# AC2_Measure.net
KiCad netlist of a schematic drawn in Altium Designer
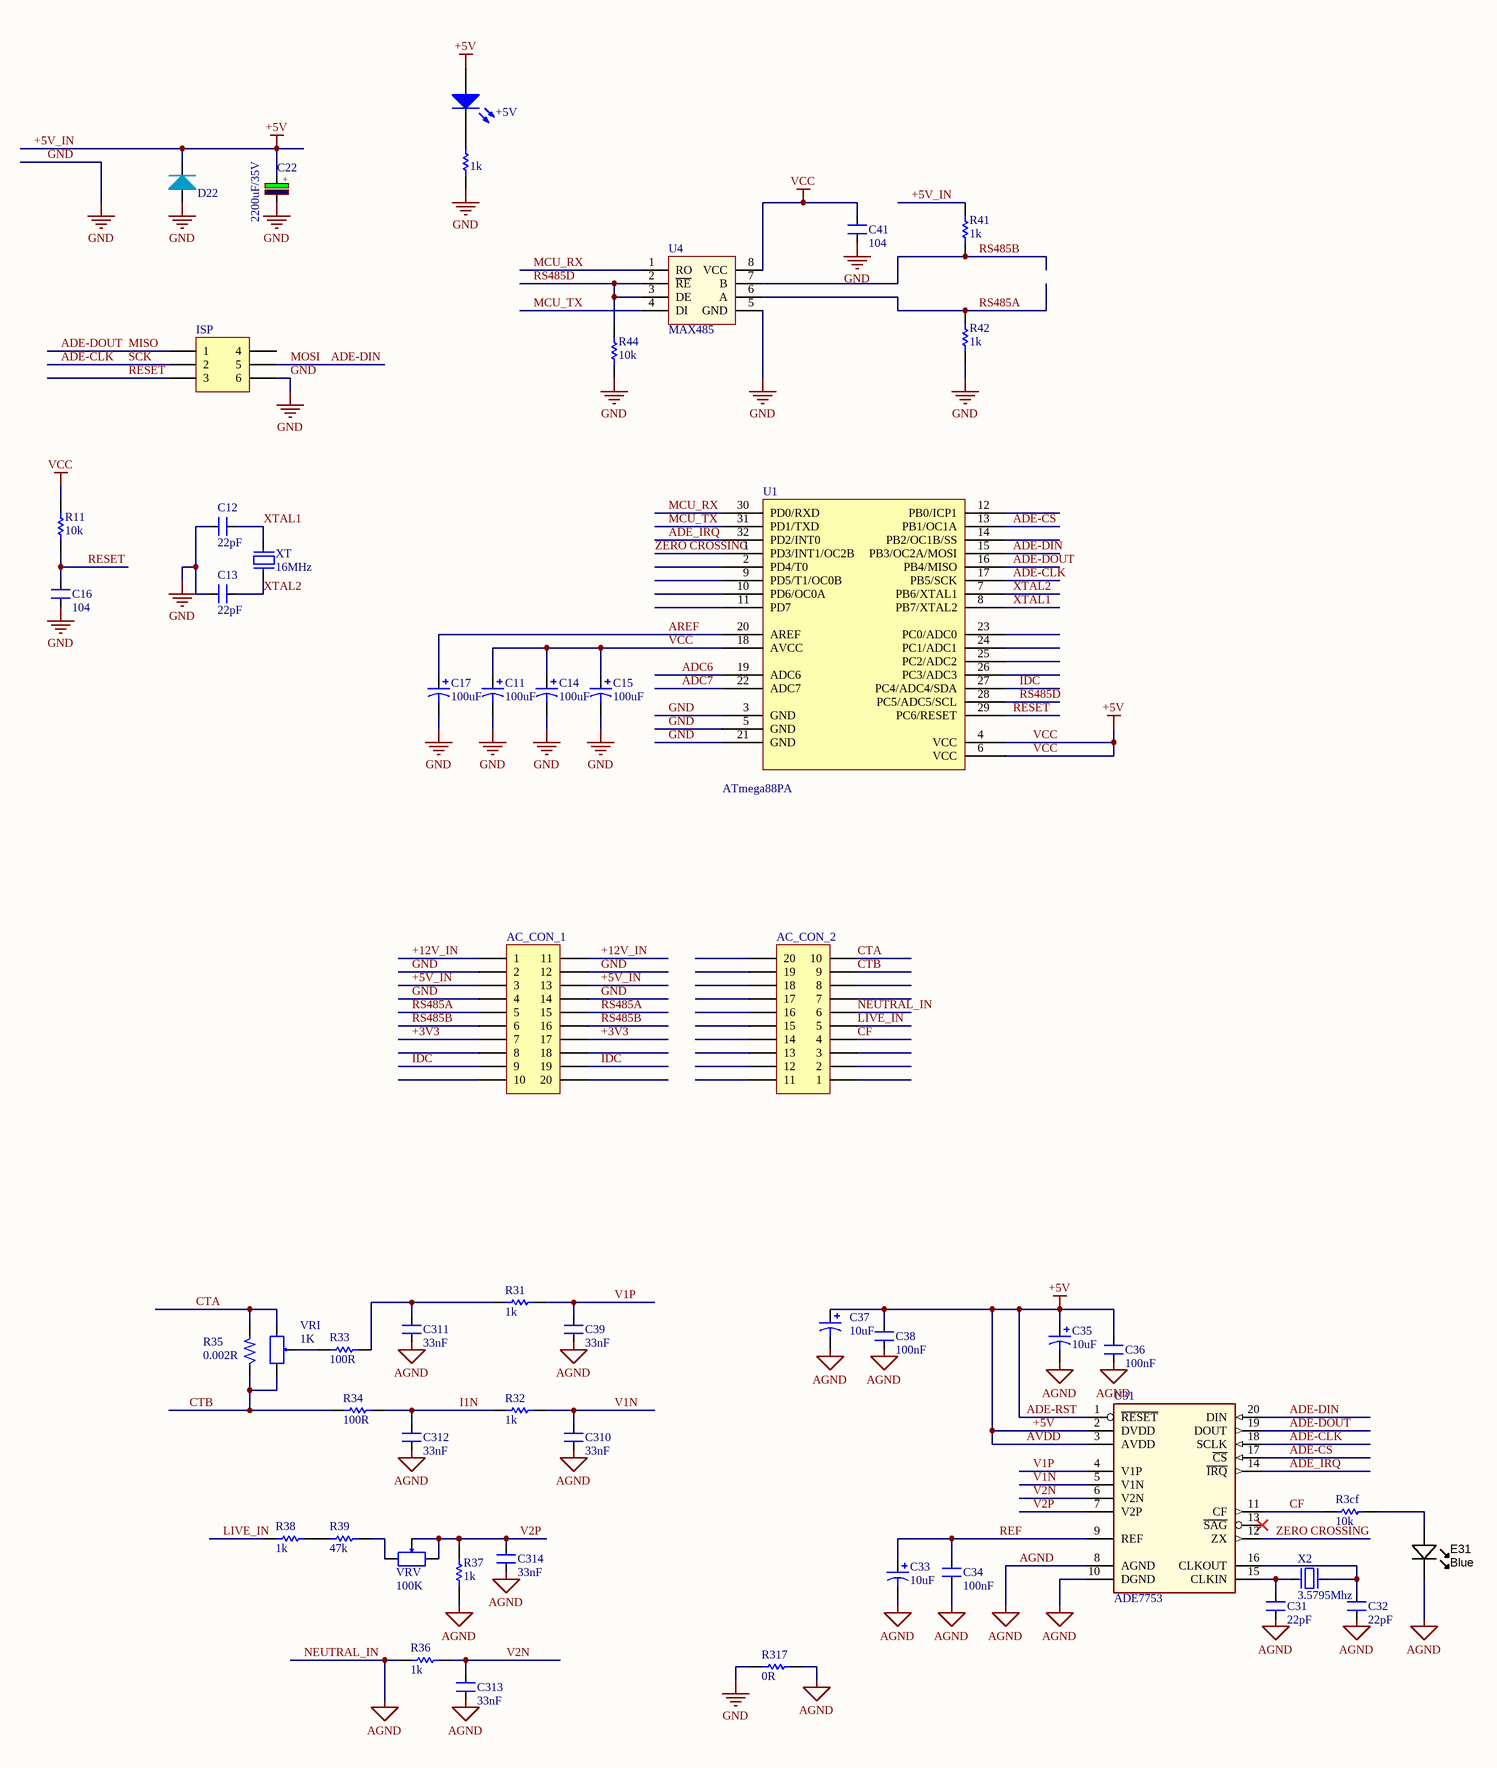
[diagram p0: AC2_Measure.SchDoc]

(export (version "E")
  (design (tool "Eeschema 10.0.6"))
  (components
    (comp (ref "+5V") (value "Led") (footprint "LED 5mm RED") (libsource (lib "Tuan") (part "Led")))
    (comp (ref "AC_CON_1")
      (value "Header 10X2A")
      (footprint "OMC10")
      (description "Header, 10-Pin, Dual row")
      (fields (field (name "PUBLISHER") "Altium Limited"))
      (libsource (lib "Miscellaneous Connectors") (part "Header 10X2A"))
    )
    (comp (ref "AC_CON_2")
      (value "Header 10X2A")
      (footprint "OMC10")
      (description "Header, 10-Pin, Dual row")
      (fields (field (name "PUBLISHER") "Altium Limited"))
      (libsource (lib "") (part "Header 10X2A_1"))
    )
    (comp (ref "C11")
      (value "100uF")
      (footprint "CAPC2012N_F")
      (fields (field (name "Comment") "Cap"))
      (libsource (lib "Tuan") (part "Cap"))
    )
    (comp (ref "C12")
      (value "22pF")
      (footprint "CAPC1608N")
      (fields (field (name "Comment") "CAP NP"))
      (libsource (lib "Tuan") (part "CAP NP"))
    )
    (comp (ref "C13")
      (value "22pF")
      (footprint "CAPC1608N")
      (fields (field (name "Comment") "CAP NP"))
      (libsource (lib "Tuan") (part "CAP NP"))
    )
    (comp (ref "C14")
      (value "100uF")
      (footprint "CAPC2012N_F")
      (fields (field (name "Comment") "Cap"))
      (libsource (lib "Tuan") (part "Cap"))
    )
    (comp (ref "C15")
      (value "100uF")
      (footprint "CAPC2012N_F")
      (fields (field (name "Comment") "Cap"))
      (libsource (lib "Tuan") (part "Cap"))
    )
    (comp (ref "C16")
      (value "104")
      (footprint "CAPC1608N")
      (fields (field (name "Comment") "CAP NP"))
      (libsource (lib "Tuan") (part "CAP NP"))
    )
    (comp (ref "C17")
      (value "100uF")
      (footprint "CAPC2012N_F")
      (fields (field (name "Comment") "Cap"))
      (libsource (lib "Tuan") (part "Cap"))
    )
    (comp (ref "C22")
      (value "2200uF/35V")
      (footprint "PBL - SMD Packages:CAP_ELEC_SIZE_G")
      (description "Cap 1000uF/16V - 220uF/50V")
      (libsource (lib "heromap") (part "CP4"))
    )
    (comp (ref "C31")
      (value "22pF")
      (footprint "CAPC1608N")
      (fields (field (name "Comment") "CAP NP"))
      (libsource (lib "ELS-PLC-2.0") (part "CAP NP"))
    )
    (comp (ref "C32")
      (value "22pF")
      (footprint "CAPC1608N")
      (fields (field (name "Comment") "CAP NP"))
      (libsource (lib "ELS-PLC-2.0") (part "CAP NP"))
    )
    (comp (ref "C33")
      (value "10uF")
      (footprint "CAPC2012N_F")
      (fields (field (name "Comment") "Cap"))
      (libsource (lib "Tuan") (part "Cap"))
    )
    (comp (ref "C34")
      (value "100nF")
      (footprint "CAPC1608N")
      (fields (field (name "Comment") "CAP NP"))
      (libsource (lib "ELS-PLC-2.0") (part "CAP NP"))
    )
    (comp (ref "C35")
      (value "10uF")
      (footprint "CAPC2012N_F")
      (fields (field (name "Comment") "Cap"))
      (libsource (lib "Tuan") (part "Cap"))
    )
    (comp (ref "C36")
      (value "100nF")
      (footprint "CAPC1608N")
      (fields (field (name "Comment") "CAP NP"))
      (libsource (lib "ELS-PLC-2.0") (part "CAP NP"))
    )
    (comp (ref "C37")
      (value "10uF")
      (footprint "CAPC2012N_F")
      (fields (field (name "Comment") "Cap"))
      (libsource (lib "Tuan") (part "Cap"))
    )
    (comp (ref "C38")
      (value "100nF")
      (footprint "CAPC1608N")
      (fields (field (name "Comment") "CAP NP"))
      (libsource (lib "ELS-PLC-2.0") (part "CAP NP"))
    )
    (comp (ref "C39")
      (value "33nF")
      (footprint "CAPC1608N")
      (fields (field (name "Comment") "CAP NP"))
      (libsource (lib "ELS-PLC-2.0") (part "CAP NP"))
    )
    (comp (ref "C41")
      (value "104")
      (footprint "CAPC2012N_F")
      (fields (field (name "Comment") "100nF/104"))
      (libsource (lib "Tuan") (part "CAP NP"))
    )
    (comp (ref "C310")
      (value "33nF")
      (footprint "CAPC1608N")
      (fields (field (name "Comment") "CAP NP"))
      (libsource (lib "ELS-PLC-2.0") (part "CAP NP"))
    )
    (comp (ref "C311")
      (value "33nF")
      (footprint "CAPC1608N")
      (fields (field (name "Comment") "CAP NP"))
      (libsource (lib "ELS-PLC-2.0") (part "CAP NP"))
    )
    (comp (ref "C312")
      (value "33nF")
      (footprint "CAPC1608N")
      (fields (field (name "Comment") "CAP NP"))
      (libsource (lib "ELS-PLC-2.0") (part "CAP NP"))
    )
    (comp (ref "C313")
      (value "33nF")
      (footprint "CAPC1608N")
      (fields (field (name "Comment") "CAP NP"))
      (libsource (lib "ELS-PLC-2.0") (part "CAP NP"))
    )
    (comp (ref "C314")
      (value "33nF")
      (footprint "CAPC1608N")
      (fields (field (name "Comment") "CAP NP"))
      (libsource (lib "ELS-PLC-2.0") (part "CAP NP"))
    )
    (comp (ref "D22") (value "Diode") (footprint "DO-214AC") (libsource (lib "Tuan") (part "Diode")))
    (comp (ref "E31")
      (value "Blue")
      (footprint "LED-0805-K")
      (description "LED 0805 SMD Blue 100mcd 470nm")
      (fields (field (name "COLOR") "Blue"))
      (libsource (lib "PBL - Light Sources") (part "LED_SMD_Blue_0805_100mcd"))
    )
    (comp (ref "ISP")
      (value "Header 3X2A")
      (footprint "HDR2X3_CEN")
      (description "Header, 3-Pin, Dual row")
      (fields (field (name "PUBLISHER") "Altium Limited"))
      (libsource (lib "Miscellaneous Connectors") (part "Header 3X2A"))
    )
    (comp (ref "R3cf")
      (value "10k")
      (footprint "0603ESDA")
      (fields (field (name "Comment") "Res"))
      (libsource (lib "Tuan") (part "Res"))
    )
    (comp (ref "R11")
      (value "10k")
      (footprint "RESC1608N_ZERO")
      (fields (field (name "Comment") "Res"))
      (libsource (lib "Tuan") (part "Res"))
    )
    (comp (ref "R22")
      (value "1k")
      (footprint "RESC2012N_F")
      (fields (field (name "Comment") "Res_0805_1k"))
      (libsource (lib "Tuan") (part "Res"))
    )
    (comp (ref "R31")
      (value "1k")
      (footprint "0603ESDA")
      (fields (field (name "Comment") "Res"))
      (libsource (lib "Tuan") (part "Res"))
    )
    (comp (ref "R32")
      (value "1k")
      (footprint "0603ESDA")
      (fields (field (name "Comment") "Res"))
      (libsource (lib "Tuan") (part "Res"))
    )
    (comp (ref "R33")
      (value "100R")
      (footprint "0603ESDA")
      (fields (field (name "Comment") "Res"))
      (libsource (lib "Tuan") (part "Res"))
    )
    (comp (ref "R34")
      (value "100R")
      (footprint "0603ESDA")
      (fields (field (name "Comment") "Res"))
      (libsource (lib "Tuan") (part "Res"))
    )
    (comp (ref "R35")
      (value "0.002R")
      (footprint "RESC6332N")
      (description "Resistor 1/4W")
      (libsource (lib "syhaunguyen") (part "R"))
    )
    (comp (ref "R36")
      (value "1k")
      (footprint "0603ESDA")
      (fields (field (name "Comment") "Res"))
      (libsource (lib "Tuan") (part "Res"))
    )
    (comp (ref "R37")
      (value "1k")
      (footprint "0603ESDA")
      (fields (field (name "Comment") "Res"))
      (libsource (lib "Tuan") (part "Res"))
    )
    (comp (ref "R38")
      (value "1k")
      (footprint "RESC2012N_F")
      (fields (field (name "Comment") "Res"))
      (libsource (lib "Tuan") (part "Res"))
    )
    (comp (ref "R39")
      (value "47k")
      (footprint "RESC2012N_F")
      (fields (field (name "Comment") "Res"))
      (libsource (lib "Tuan") (part "Res"))
    )
    (comp (ref "R41")
      (value "1k")
      (footprint "RESC1608N_ZERO")
      (description "Tro dan")
      (libsource (lib "GPS_Clock_v12") (part "Res"))
    )
    (comp (ref "R42")
      (value "1k")
      (footprint "RESC1608N_ZERO")
      (description "Tro dan")
      (libsource (lib "GPS_Clock_v12") (part "Res"))
    )
    (comp (ref "R44")
      (value "10k")
      (footprint "RESC1608N_ZERO")
      (description "Tro dan")
      (fields (field (name "Comment") "330R"))
      (libsource (lib "GPS_Clock_v12") (part "Res"))
    )
    (comp (ref "R317")
      (value "0R")
      (footprint "RESC2012N_F")
      (fields (field (name "Comment") "Res"))
      (libsource (lib "Tuan") (part "Res"))
    )
    (comp (ref "U1")
      (value "ATmega88PA")
      (footprint "32PIN")
      (description "ATmega48/168/328")
      (libsource (lib "Tuan") (part "ATmega48/168/328"))
    )
    (comp (ref "U4")
      (value "MAX485")
      (footprint "SO-8")
      (description "RS232 - RS485 (Same sn75176)")
      (libsource (lib "heromap") (part "MAX485"))
    )
    (comp (ref "U31")
      (value "ADE7753")
      (footprint "TSSOP-20")
      (description "Single-Phase Multifunction Metering IC with di/dt Sensor Interface")
      (libsource (lib "heromap") (part "ADE7753"))
    )
    (comp (ref "VRI")
      (value "1K")
      (footprint "heromap:VR1")
      (description "Var Resistor")
      (libsource (lib "heromap") (part "VR"))
    )
    (comp (ref "VRV")
      (value "100K")
      (footprint "heromap:VR1")
      (description "Var Resistor")
      (libsource (lib "heromap") (part "VR"))
    )
    (comp (ref "X2")
      (value "3.5795Mhz")
      (footprint "heromap:XT2")
      (description "Crystal For all Crystal 2pin.")
      (libsource (lib "heromap") (part "XT2"))
    )
    (comp (ref "XT") (value "16MHz") (footprint "XT2") (libsource (lib "Tuan") (part "Crystal")))
  )
  (nets
    (net (code "1") (name "+5V") (class "Default")
      (node (ref "+5V") (pin "1") (pinfunction "A_1") (pintype "passive"))
      (node (ref "AC_CON_1") (pin "13") (pinfunction "13_13") (pintype "passive"))
      (node (ref "AC_CON_1") (pin "3") (pinfunction "3_3") (pintype "passive"))
      (node (ref "C11") (pin "1") (pinfunction "1_1") (pintype "passive"))
      (node (ref "C14") (pin "1") (pinfunction "1_1") (pintype "passive"))
      (node (ref "C15") (pin "1") (pinfunction "1_1") (pintype "passive"))
      (node (ref "C22") (pin "1") (pinfunction "1_1") (pintype "passive"))
      (node (ref "C35") (pin "1") (pinfunction "1_1") (pintype "passive"))
      (node (ref "C36") (pin "2") (pinfunction "2_2") (pintype "passive"))
      (node (ref "C37") (pin "1") (pinfunction "1_1") (pintype "passive"))
      (node (ref "C38") (pin "2") (pinfunction "2_2") (pintype "passive"))
      (node (ref "C41") (pin "2") (pinfunction "2_2") (pintype "passive"))
      (node (ref "D22") (pin "2") (pinfunction "K_2") (pintype "passive"))
      (node (ref "R11") (pin "2") (pinfunction "2_2") (pintype "passive"))
      (node (ref "R41") (pin "2") (pinfunction "2_2") (pintype "passive"))
      (node (ref "U1") (pin "18") (pinfunction "AVCC_18") (pintype "passive"))
      (node (ref "U1") (pin "4") (pinfunction "VCC_4") (pintype "passive"))
      (node (ref "U1") (pin "6") (pinfunction "VCC_6") (pintype "passive"))
      (node (ref "U31") (pin "1") (pinfunction "~{RESET}_1") (pintype "passive"))
      (node (ref "U31") (pin "2") (pinfunction "DVDD_2") (pintype "passive"))
      (node (ref "U31") (pin "3") (pinfunction "AVDD_3") (pintype "passive"))
      (node (ref "U4") (pin "8") (pinfunction "VCC_8") (pintype "passive"))
    )
    (net (code "2") (name "/+3V3") (class "Default")
      (node (ref "AC_CON_1") (pin "17") (pinfunction "17_17") (pintype "passive"))
      (node (ref "AC_CON_1") (pin "7") (pinfunction "7_7") (pintype "passive"))
    )
    (net (code "3") (name "/+12V_IN") (class "Default")
      (node (ref "AC_CON_1") (pin "1") (pinfunction "1_1") (pintype "passive"))
      (node (ref "AC_CON_1") (pin "11") (pinfunction "11_11") (pintype "passive"))
    )
    (net (code "4") (name "/ADC6") (class "Default")
      (node (ref "U1") (pin "19") (pinfunction "ADC6_19") (pintype "passive"))
    )
    (net (code "5") (name "/ADC7") (class "Default")
      (node (ref "U1") (pin "22") (pinfunction "ADC7_22") (pintype "passive"))
    )
    (net (code "6") (name "/ADE-CLK") (class "Default")
      (node (ref "ISP") (pin "2") (pinfunction "2_2") (pintype "passive"))
      (node (ref "U1") (pin "17") (pinfunction "PB5/SCK_17") (pintype "passive"))
      (node (ref "U31") (pin "18") (pinfunction "SCLK_18") (pintype "input"))
    )
    (net (code "7") (name "/ADE-CS") (class "Default")
      (node (ref "U1") (pin "13") (pinfunction "PB1/OC1A_13") (pintype "passive"))
      (node (ref "U31") (pin "17") (pinfunction "~{CS}_17") (pintype "input"))
    )
    (net (code "8") (name "/ADE-DIN") (class "Default")
      (node (ref "ISP") (pin "5") (pinfunction "5_5") (pintype "passive"))
      (node (ref "U1") (pin "15") (pinfunction "PB3/OC2A/MOSI_15") (pintype "passive"))
      (node (ref "U31") (pin "20") (pinfunction "DIN_20") (pintype "input"))
    )
    (net (code "9") (name "/ADE-DOUT") (class "Default")
      (node (ref "ISP") (pin "1") (pinfunction "1_1") (pintype "passive"))
      (node (ref "U1") (pin "16") (pinfunction "PB4/MISO_16") (pintype "passive"))
      (node (ref "U31") (pin "19") (pinfunction "DOUT_19") (pintype "output"))
    )
    (net (code "10") (name "/ADE_IRQ") (class "Default")
      (node (ref "U1") (pin "32") (pinfunction "PD2/INT0_32") (pintype "passive"))
      (node (ref "U31") (pin "14") (pinfunction "~{IRQ}_14") (pintype "output"))
    )
    (net (code "11") (name "/AREF") (class "Default")
      (node (ref "C17") (pin "1") (pinfunction "1_1") (pintype "passive"))
      (node (ref "U1") (pin "20") (pinfunction "AREF_20") (pintype "passive"))
    )
    (net (code "12") (name "/CF") (class "Default")
      (node (ref "AC_CON_2") (pin "4") (pinfunction "4_4") (pintype "passive"))
      (node (ref "R3cf") (pin "1") (pinfunction "1_1") (pintype "passive"))
      (node (ref "U31") (pin "11") (pinfunction "CF_11") (pintype "output"))
    )
    (net (code "13") (name "/CTA") (class "Default")
      (node (ref "AC_CON_2") (pin "10") (pinfunction "10_10") (pintype "passive"))
      (node (ref "R35") (pin "2") (pinfunction "2_2") (pintype "passive"))
      (node (ref "VRI") (pin "1") (pinfunction "1_1") (pintype "passive"))
    )
    (net (code "14") (name "/CTB") (class "Default")
      (node (ref "AC_CON_2") (pin "9") (pinfunction "9_9") (pintype "passive"))
      (node (ref "R34") (pin "1") (pinfunction "1_1") (pintype "passive"))
      (node (ref "R35") (pin "1") (pinfunction "1_1") (pintype "passive"))
      (node (ref "VRI") (pin "3") (pinfunction "3_3") (pintype "passive"))
    )
    (net (code "15") (name "/I1N") (class "Default")
      (node (ref "C312") (pin "2") (pinfunction "2_2") (pintype "passive"))
      (node (ref "R32") (pin "1") (pinfunction "1_1") (pintype "passive"))
      (node (ref "R34") (pin "2") (pinfunction "2_2") (pintype "passive"))
    )
    (net (code "16") (name "/IDC") (class "Default")
      (node (ref "AC_CON_1") (pin "19") (pinfunction "19_19") (pintype "passive"))
      (node (ref "AC_CON_1") (pin "9") (pinfunction "9_9") (pintype "passive"))
      (node (ref "U1") (pin "27") (pinfunction "PC4/ADC4/SDA_27") (pintype "passive"))
    )
    (net (code "17") (name "/LIVE_IN") (class "Default")
      (node (ref "AC_CON_2") (pin "5") (pinfunction "5_5") (pintype "passive"))
      (node (ref "R38") (pin "1") (pinfunction "1_1") (pintype "passive"))
    )
    (net (code "18") (name "/MCU_RX") (class "Default")
      (node (ref "U1") (pin "30") (pinfunction "PD0/RXD_30") (pintype "passive"))
      (node (ref "U4") (pin "1") (pinfunction "RO_1") (pintype "passive"))
    )
    (net (code "19") (name "/MCU_TX") (class "Default")
      (node (ref "U1") (pin "31") (pinfunction "PD1/TXD_31") (pintype "passive"))
      (node (ref "U4") (pin "4") (pinfunction "DI_4") (pintype "passive"))
    )
    (net (code "20") (name "/REF") (class "Default")
      (node (ref "C33") (pin "1") (pinfunction "1_1") (pintype "passive"))
      (node (ref "C34") (pin "2") (pinfunction "2_2") (pintype "passive"))
      (node (ref "U31") (pin "9") (pinfunction "REF_9") (pintype "passive"))
    )
    (net (code "21") (name "/RESET") (class "Default")
      (node (ref "C16") (pin "2") (pinfunction "2_2") (pintype "passive"))
      (node (ref "ISP") (pin "3") (pinfunction "3_3") (pintype "passive"))
      (node (ref "R11") (pin "1") (pinfunction "1_1") (pintype "passive"))
      (node (ref "U1") (pin "29") (pinfunction "PC6/RESET_29") (pintype "passive"))
    )
    (net (code "22") (name "/RS485A") (class "Default")
      (node (ref "AC_CON_1") (pin "15") (pinfunction "15_15") (pintype "passive"))
      (node (ref "AC_CON_1") (pin "5") (pinfunction "5_5") (pintype "passive"))
      (node (ref "R42") (pin "2") (pinfunction "2_2") (pintype "passive"))
      (node (ref "U4") (pin "6") (pinfunction "A_6") (pintype "passive"))
    )
    (net (code "23") (name "/RS485B") (class "Default")
      (node (ref "AC_CON_1") (pin "16") (pinfunction "16_16") (pintype "passive"))
      (node (ref "AC_CON_1") (pin "6") (pinfunction "6_6") (pintype "passive"))
      (node (ref "R41") (pin "1") (pinfunction "1_1") (pintype "passive"))
      (node (ref "U4") (pin "7") (pinfunction "B_7") (pintype "passive"))
    )
    (net (code "24") (name "/RS485D") (class "Default")
      (node (ref "R44") (pin "2") (pinfunction "2_2") (pintype "passive"))
      (node (ref "U1") (pin "28") (pinfunction "PC5/ADC5/SCL_28") (pintype "passive"))
      (node (ref "U4") (pin "2") (pinfunction "~{RE}_2") (pintype "passive"))
      (node (ref "U4") (pin "3") (pinfunction "DE_3") (pintype "passive"))
    )
    (net (code "25") (name "/V1N") (class "Default")
      (node (ref "C310") (pin "2") (pinfunction "2_2") (pintype "passive"))
      (node (ref "R32") (pin "2") (pinfunction "2_2") (pintype "passive"))
      (node (ref "U31") (pin "5") (pinfunction "V1N_5") (pintype "passive"))
    )
    (net (code "26") (name "/V1P") (class "Default")
      (node (ref "C39") (pin "2") (pinfunction "2_2") (pintype "passive"))
      (node (ref "R31") (pin "2") (pinfunction "2_2") (pintype "passive"))
      (node (ref "U31") (pin "4") (pinfunction "V1P_4") (pintype "passive"))
    )
    (net (code "27") (name "/V2N") (class "Default")
      (node (ref "C313") (pin "2") (pinfunction "2_2") (pintype "passive"))
      (node (ref "R36") (pin "2") (pinfunction "2_2") (pintype "passive"))
      (node (ref "U31") (pin "6") (pinfunction "V2N_6") (pintype "passive"))
    )
    (net (code "28") (name "/V2P") (class "Default")
      (node (ref "C314") (pin "2") (pinfunction "2_2") (pintype "passive"))
      (node (ref "R37") (pin "2") (pinfunction "2_2") (pintype "passive"))
      (node (ref "U31") (pin "7") (pinfunction "V2P_7") (pintype "passive"))
      (node (ref "VRV") (pin "2") (pinfunction "2_2") (pintype "passive"))
      (node (ref "VRV") (pin "3") (pinfunction "3_3") (pintype "passive"))
    )
    (net (code "29") (name "/XTAL1") (class "Default")
      (node (ref "C12") (pin "1") (pinfunction "1_1") (pintype "passive"))
      (node (ref "U1") (pin "8") (pinfunction "PB7/XTAL2_8") (pintype "passive"))
      (node (ref "XT") (pin "2") (pinfunction "2_2") (pintype "passive"))
    )
    (net (code "30") (name "/XTAL2") (class "Default")
      (node (ref "C13") (pin "1") (pinfunction "1_1") (pintype "passive"))
      (node (ref "U1") (pin "7") (pinfunction "PB6/XTAL1_7") (pintype "passive"))
      (node (ref "XT") (pin "1") (pinfunction "1_1") (pintype "passive"))
    )
    (net (code "31") (name "/ZERO CROSSING") (class "Default")
      (node (ref "U1") (pin "1") (pinfunction "PD3/INT1/OC2B_1") (pintype "passive"))
      (node (ref "U31") (pin "12") (pinfunction "ZX_12") (pintype "output"))
    )
    (net (code "32") (name "AGND") (class "Default")
      (node (ref "AC_CON_2") (pin "6") (pinfunction "6_6") (pintype "passive"))
      (node (ref "C31") (pin "1") (pinfunction "1_1") (pintype "passive"))
      (node (ref "C310") (pin "1") (pinfunction "1_1") (pintype "passive"))
      (node (ref "C311") (pin "1") (pinfunction "1_1") (pintype "passive"))
      (node (ref "C312") (pin "1") (pinfunction "1_1") (pintype "passive"))
      (node (ref "C313") (pin "1") (pinfunction "1_1") (pintype "passive"))
      (node (ref "C314") (pin "1") (pinfunction "1_1") (pintype "passive"))
      (node (ref "C32") (pin "1") (pinfunction "1_1") (pintype "passive"))
      (node (ref "C33") (pin "2") (pinfunction "2_2") (pintype "passive"))
      (node (ref "C34") (pin "1") (pinfunction "1_1") (pintype "passive"))
      (node (ref "C35") (pin "2") (pinfunction "2_2") (pintype "passive"))
      (node (ref "C36") (pin "1") (pinfunction "1_1") (pintype "passive"))
      (node (ref "C37") (pin "2") (pinfunction "2_2") (pintype "passive"))
      (node (ref "C38") (pin "1") (pinfunction "1_1") (pintype "passive"))
      (node (ref "C39") (pin "1") (pinfunction "1_1") (pintype "passive"))
      (node (ref "E31") (pin "K") (pinfunction "K_K") (pintype "passive"))
      (node (ref "R317") (pin "2") (pinfunction "2_2") (pintype "passive"))
      (node (ref "R36") (pin "1") (pinfunction "1_1") (pintype "passive"))
      (node (ref "R37") (pin "1") (pinfunction "1_1") (pintype "passive"))
      (node (ref "U31") (pin "10") (pinfunction "DGND_10") (pintype "passive"))
      (node (ref "U31") (pin "8") (pinfunction "AGND_8") (pintype "passive"))
    )
    (net (code "33") (name "GND") (class "Default")
      (node (ref "AC_CON_1") (pin "12") (pinfunction "12_12") (pintype "passive"))
      (node (ref "AC_CON_1") (pin "14") (pinfunction "14_14") (pintype "passive"))
      (node (ref "AC_CON_1") (pin "2") (pinfunction "2_2") (pintype "passive"))
      (node (ref "AC_CON_1") (pin "4") (pinfunction "4_4") (pintype "passive"))
      (node (ref "C11") (pin "2") (pinfunction "2_2") (pintype "passive"))
      (node (ref "C12") (pin "2") (pinfunction "2_2") (pintype "passive"))
      (node (ref "C13") (pin "2") (pinfunction "2_2") (pintype "passive"))
      (node (ref "C14") (pin "2") (pinfunction "2_2") (pintype "passive"))
      (node (ref "C15") (pin "2") (pinfunction "2_2") (pintype "passive"))
      (node (ref "C16") (pin "1") (pinfunction "1_1") (pintype "passive"))
      (node (ref "C17") (pin "2") (pinfunction "2_2") (pintype "passive"))
      (node (ref "C22") (pin "2") (pinfunction "2_2") (pintype "passive"))
      (node (ref "C41") (pin "1") (pinfunction "1_1") (pintype "passive"))
      (node (ref "D22") (pin "1") (pinfunction "A_1") (pintype "passive"))
      (node (ref "ISP") (pin "6") (pinfunction "6_6") (pintype "passive"))
      (node (ref "R22") (pin "2") (pinfunction "2_2") (pintype "passive"))
      (node (ref "R317") (pin "1") (pinfunction "1_1") (pintype "passive"))
      (node (ref "R42") (pin "1") (pinfunction "1_1") (pintype "passive"))
      (node (ref "R44") (pin "1") (pinfunction "1_1") (pintype "passive"))
      (node (ref "U1") (pin "21") (pinfunction "GND_21") (pintype "power_in"))
      (node (ref "U1") (pin "3") (pinfunction "GND_3") (pintype "power_in"))
      (node (ref "U1") (pin "5") (pinfunction "GND_5") (pintype "power_in"))
      (node (ref "U4") (pin "5") (pinfunction "GND_5") (pintype "passive"))
    )
    (net (code "34") (name "Net-(+5V-K)") (class "Default")
      (node (ref "+5V") (pin "2") (pinfunction "K_2") (pintype "passive"))
      (node (ref "R22") (pin "1") (pinfunction "1_1") (pintype "passive"))
    )
    (net (code "35") (name "Net-(C311-Pad2)") (class "Default")
      (node (ref "C311") (pin "2") (pinfunction "2_2") (pintype "passive"))
      (node (ref "R31") (pin "1") (pinfunction "1_1") (pintype "passive"))
      (node (ref "R33") (pin "2") (pinfunction "2_2") (pintype "passive"))
    )
    (net (code "36") (name "Net-(E31-PadA)") (class "Default")
      (node (ref "E31") (pin "A") (pinfunction "A_A") (pintype "passive"))
      (node (ref "R3cf") (pin "2") (pinfunction "2_2") (pintype "passive"))
    )
    (net (code "37") (name "Net-(R33-Pad1)") (class "Default")
      (node (ref "R33") (pin "1") (pinfunction "1_1") (pintype "passive"))
      (node (ref "VRI") (pin "2") (pinfunction "2_2") (pintype "passive"))
    )
    (net (code "38") (name "Net-(R38-Pad2)") (class "Default")
      (node (ref "R38") (pin "2") (pinfunction "2_2") (pintype "passive"))
      (node (ref "R39") (pin "1") (pinfunction "1_1") (pintype "passive"))
    )
    (net (code "39") (name "Net-(R39-Pad2)") (class "Default")
      (node (ref "R39") (pin "2") (pinfunction "2_2") (pintype "passive"))
      (node (ref "VRV") (pin "1") (pinfunction "1_1") (pintype "passive"))
    )
    (net (code "40") (name "Net-(U31-CLKIN)") (class "Default")
      (node (ref "C31") (pin "2") (pinfunction "2_2") (pintype "passive"))
      (node (ref "U31") (pin "15") (pinfunction "CLKIN_15") (pintype "passive"))
      (node (ref "X2") (pin "2") (pinfunction "2_2") (pintype "passive"))
    )
    (net (code "41") (name "Net-(U31-CLKOUT)") (class "Default")
      (node (ref "C32") (pin "2") (pinfunction "2_2") (pintype "passive"))
      (node (ref "U31") (pin "16") (pinfunction "CLKOUT_16") (pintype "passive"))
      (node (ref "X2") (pin "1") (pinfunction "1_1") (pintype "passive"))
    )
    (net (code "42") (name "unconnected-(AC_CON_1-Pad8)") (class "Default")
      (node (ref "AC_CON_1") (pin "8") (pinfunction "8_8") (pintype "passive"))
    )
    (net (code "43") (name "unconnected-(AC_CON_1-Pad10)") (class "Default")
      (node (ref "AC_CON_1") (pin "10") (pinfunction "10_10") (pintype "passive"))
    )
    (net (code "44") (name "unconnected-(AC_CON_1-Pad18)") (class "Default")
      (node (ref "AC_CON_1") (pin "18") (pinfunction "18_18") (pintype "passive"))
    )
    (net (code "45") (name "unconnected-(AC_CON_1-Pad20)") (class "Default")
      (node (ref "AC_CON_1") (pin "20") (pinfunction "20_20") (pintype "passive"))
    )
    (net (code "46") (name "unconnected-(AC_CON_2-Pad1)") (class "Default")
      (node (ref "AC_CON_2") (pin "1") (pinfunction "1_1") (pintype "passive"))
    )
    (net (code "47") (name "unconnected-(AC_CON_2-Pad2)") (class "Default")
      (node (ref "AC_CON_2") (pin "2") (pinfunction "2_2") (pintype "passive"))
    )
    (net (code "48") (name "unconnected-(AC_CON_2-Pad3)") (class "Default")
      (node (ref "AC_CON_2") (pin "3") (pinfunction "3_3") (pintype "passive"))
    )
    (net (code "49") (name "unconnected-(AC_CON_2-Pad7)") (class "Default")
      (node (ref "AC_CON_2") (pin "7") (pinfunction "7_7") (pintype "passive"))
    )
    (net (code "50") (name "unconnected-(AC_CON_2-Pad8)") (class "Default")
      (node (ref "AC_CON_2") (pin "8") (pinfunction "8_8") (pintype "passive"))
    )
    (net (code "51") (name "unconnected-(AC_CON_2-Pad11)") (class "Default")
      (node (ref "AC_CON_2") (pin "11") (pinfunction "11_11") (pintype "passive"))
    )
    (net (code "52") (name "unconnected-(AC_CON_2-Pad12)") (class "Default")
      (node (ref "AC_CON_2") (pin "12") (pinfunction "12_12") (pintype "passive"))
    )
    (net (code "53") (name "unconnected-(AC_CON_2-Pad13)") (class "Default")
      (node (ref "AC_CON_2") (pin "13") (pinfunction "13_13") (pintype "passive"))
    )
    (net (code "54") (name "unconnected-(AC_CON_2-Pad14)") (class "Default")
      (node (ref "AC_CON_2") (pin "14") (pinfunction "14_14") (pintype "passive"))
    )
    (net (code "55") (name "unconnected-(AC_CON_2-Pad15)") (class "Default")
      (node (ref "AC_CON_2") (pin "15") (pinfunction "15_15") (pintype "passive"))
    )
    (net (code "56") (name "unconnected-(AC_CON_2-Pad16)") (class "Default")
      (node (ref "AC_CON_2") (pin "16") (pinfunction "16_16") (pintype "passive"))
    )
    (net (code "57") (name "unconnected-(AC_CON_2-Pad17)") (class "Default")
      (node (ref "AC_CON_2") (pin "17") (pinfunction "17_17") (pintype "passive"))
    )
    (net (code "58") (name "unconnected-(AC_CON_2-Pad18)") (class "Default")
      (node (ref "AC_CON_2") (pin "18") (pinfunction "18_18") (pintype "passive"))
    )
    (net (code "59") (name "unconnected-(AC_CON_2-Pad19)") (class "Default")
      (node (ref "AC_CON_2") (pin "19") (pinfunction "19_19") (pintype "passive"))
    )
    (net (code "60") (name "unconnected-(AC_CON_2-Pad20)") (class "Default")
      (node (ref "AC_CON_2") (pin "20") (pinfunction "20_20") (pintype "passive"))
    )
    (net (code "61") (name "unconnected-(ISP-Pad4)") (class "Default")
      (node (ref "ISP") (pin "4") (pinfunction "4_4") (pintype "passive"))
    )
    (net (code "62") (name "unconnected-(U1-PB0{slash}ICP1-Pad12)") (class "Default")
      (node (ref "U1") (pin "12") (pinfunction "PB0/ICP1_12") (pintype "passive"))
    )
    (net (code "63") (name "unconnected-(U1-PB2{slash}OC1B{slash}SS-Pad14)") (class "Default")
      (node (ref "U1") (pin "14") (pinfunction "PB2/OC1B/SS_14") (pintype "passive"))
    )
    (net (code "64") (name "unconnected-(U1-PC0{slash}ADC0-Pad23)") (class "Default")
      (node (ref "U1") (pin "23") (pinfunction "PC0/ADC0_23") (pintype "passive"))
    )
    (net (code "65") (name "unconnected-(U1-PC1{slash}ADC1-Pad24)") (class "Default")
      (node (ref "U1") (pin "24") (pinfunction "PC1/ADC1_24") (pintype "passive"))
    )
    (net (code "66") (name "unconnected-(U1-PC2{slash}ADC2-Pad25)") (class "Default")
      (node (ref "U1") (pin "25") (pinfunction "PC2/ADC2_25") (pintype "passive"))
    )
    (net (code "67") (name "unconnected-(U1-PC3{slash}ADC3-Pad26)") (class "Default")
      (node (ref "U1") (pin "26") (pinfunction "PC3/ADC3_26") (pintype "passive"))
    )
    (net (code "68") (name "unconnected-(U1-PD4{slash}T0-Pad2)") (class "Default")
      (node (ref "U1") (pin "2") (pinfunction "PD4/T0_2") (pintype "passive"))
    )
    (net (code "69") (name "unconnected-(U1-PD5{slash}T1{slash}OC0B-Pad9)") (class "Default")
      (node (ref "U1") (pin "9") (pinfunction "PD5/T1/OC0B_9") (pintype "passive"))
    )
    (net (code "70") (name "unconnected-(U1-PD6{slash}OC0A-Pad10)") (class "Default")
      (node (ref "U1") (pin "10") (pinfunction "PD6/OC0A_10") (pintype "passive"))
    )
    (net (code "71") (name "unconnected-(U1-PD7-Pad11)") (class "Default")
      (node (ref "U1") (pin "11") (pinfunction "PD7_11") (pintype "passive"))
    )
    (net (code "72") (name "unconnected-(U31-~{SAG}-Pad13)") (class "Default")
      (node (ref "U31") (pin "13") (pinfunction "~{SAG}_13") (pintype "passive+no_connect"))
    )
  )
)
